# LED_Board.net
KiCad netlist of a schematic drawn in EAGLE
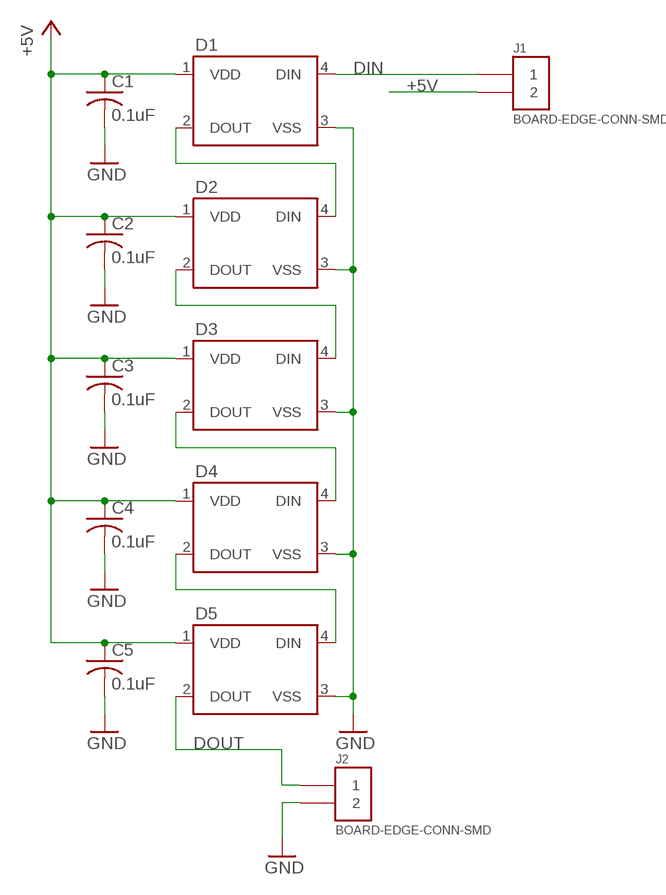
[diagram p0: schematic, sheet 1]

(export (version "E")
  (design (tool "Eeschema 10.0.6"))
  (components
    (comp (ref "C1")
      (value "0.1uF")
      (footprint "eagle-import:C0603")
      (libsource (lib "eagle-import") (part "C-USC0603"))
    )
    (comp (ref "C2")
      (value "0.1uF")
      (footprint "eagle-import:C0603")
      (libsource (lib "eagle-import") (part "C-USC0603"))
    )
    (comp (ref "C3")
      (value "0.1uF")
      (footprint "eagle-import:C0603")
      (libsource (lib "eagle-import") (part "C-USC0603"))
    )
    (comp (ref "C4")
      (value "0.1uF")
      (footprint "eagle-import:C0603")
      (libsource (lib "eagle-import") (part "C-USC0603"))
    )
    (comp (ref "C5")
      (value "0.1uF")
      (footprint "eagle-import:C0603")
      (libsource (lib "eagle-import") (part "C-USC0603"))
    )
    (comp (ref "D1")
      (value "WS2812B")
      (footprint "eagle-import:WS2812B")
      (libsource (lib "eagle-import") (part "WS2812B"))
    )
    (comp (ref "D2")
      (value "WS2812B")
      (footprint "eagle-import:WS2812B")
      (libsource (lib "eagle-import") (part "WS2812B"))
    )
    (comp (ref "D3")
      (value "WS2812B")
      (footprint "eagle-import:WS2812B")
      (libsource (lib "eagle-import") (part "WS2812B"))
    )
    (comp (ref "D4")
      (value "WS2812B")
      (footprint "eagle-import:WS2812B")
      (libsource (lib "eagle-import") (part "WS2812B"))
    )
    (comp (ref "D5")
      (value "WS2812B")
      (footprint "eagle-import:WS2812B")
      (libsource (lib "eagle-import") (part "WS2812B"))
    )
    (comp (ref "J1")
      (value "BOARD-EDGE-CONN-SMD")
      (footprint "eagle-import:SMD-2")
      (libsource (lib "eagle-import") (part "BOARD-EDGE-CONN-SMD"))
    )
    (comp (ref "J2")
      (value "BOARD-EDGE-CONN-SMD")
      (footprint "eagle-import:SMD-2")
      (libsource (lib "eagle-import") (part "BOARD-EDGE-CONN-SMD"))
    )
  )
  (nets
    (net (code "1") (name "+5V") (class "Default")
      (node (ref "C1") (pin "1") (pinfunction "1_1") (pintype "passive"))
      (node (ref "C2") (pin "1") (pinfunction "1_1") (pintype "passive"))
      (node (ref "C3") (pin "1") (pinfunction "1_1") (pintype "passive"))
      (node (ref "C4") (pin "1") (pinfunction "1_1") (pintype "passive"))
      (node (ref "C5") (pin "1") (pinfunction "1_1") (pintype "passive"))
      (node (ref "D1") (pin "1") (pinfunction "VDD_1") (pintype "power_in"))
      (node (ref "D2") (pin "1") (pinfunction "VDD_1") (pintype "power_in"))
      (node (ref "D3") (pin "1") (pinfunction "VDD_1") (pintype "power_in"))
      (node (ref "D4") (pin "1") (pinfunction "VDD_1") (pintype "power_in"))
      (node (ref "D5") (pin "1") (pinfunction "VDD_1") (pintype "power_in"))
      (node (ref "J1") (pin "P$2") (pinfunction "2_P$2") (pintype "bidirectional"))
    )
    (net (code "2") (name "/DIN") (class "Default")
      (node (ref "D1") (pin "4") (pinfunction "DIN_4") (pintype "input"))
      (node (ref "J1") (pin "P$1") (pinfunction "1_P$1") (pintype "bidirectional"))
    )
    (net (code "3") (name "/DOUT") (class "Default")
      (node (ref "D5") (pin "2") (pinfunction "DOUT_2") (pintype "output"))
      (node (ref "J2") (pin "P$1") (pinfunction "1_P$1") (pintype "bidirectional"))
    )
    (net (code "4") (name "GND") (class "Default")
      (node (ref "C1") (pin "2") (pinfunction "2_2") (pintype "passive"))
      (node (ref "C2") (pin "2") (pinfunction "2_2") (pintype "passive"))
      (node (ref "C3") (pin "2") (pinfunction "2_2") (pintype "passive"))
      (node (ref "C4") (pin "2") (pinfunction "2_2") (pintype "passive"))
      (node (ref "C5") (pin "2") (pinfunction "2_2") (pintype "passive"))
      (node (ref "D1") (pin "3") (pinfunction "VSS_3") (pintype "power_in"))
      (node (ref "D2") (pin "3") (pinfunction "VSS_3") (pintype "power_in"))
      (node (ref "D3") (pin "3") (pinfunction "VSS_3") (pintype "power_in"))
      (node (ref "D4") (pin "3") (pinfunction "VSS_3") (pintype "power_in"))
      (node (ref "D5") (pin "3") (pinfunction "VSS_3") (pintype "power_in"))
      (node (ref "J2") (pin "P$2") (pinfunction "2_P$2") (pintype "bidirectional"))
    )
    (net (code "5") (name "Net-(D1-DOUT)") (class "Default")
      (node (ref "D1") (pin "2") (pinfunction "DOUT_2") (pintype "output"))
      (node (ref "D2") (pin "4") (pinfunction "DIN_4") (pintype "input"))
    )
    (net (code "6") (name "Net-(D2-DOUT)") (class "Default")
      (node (ref "D2") (pin "2") (pinfunction "DOUT_2") (pintype "output"))
      (node (ref "D3") (pin "4") (pinfunction "DIN_4") (pintype "input"))
    )
    (net (code "7") (name "Net-(D3-DOUT)") (class "Default")
      (node (ref "D3") (pin "2") (pinfunction "DOUT_2") (pintype "output"))
      (node (ref "D4") (pin "4") (pinfunction "DIN_4") (pintype "input"))
    )
    (net (code "8") (name "Net-(D4-DOUT)") (class "Default")
      (node (ref "D4") (pin "2") (pinfunction "DOUT_2") (pintype "output"))
      (node (ref "D5") (pin "4") (pinfunction "DIN_4") (pintype "input"))
    )
  )
)
